# BV10011_ControlEtherCAT.net
KiCad netlist of a schematic drawn in Altium Designer
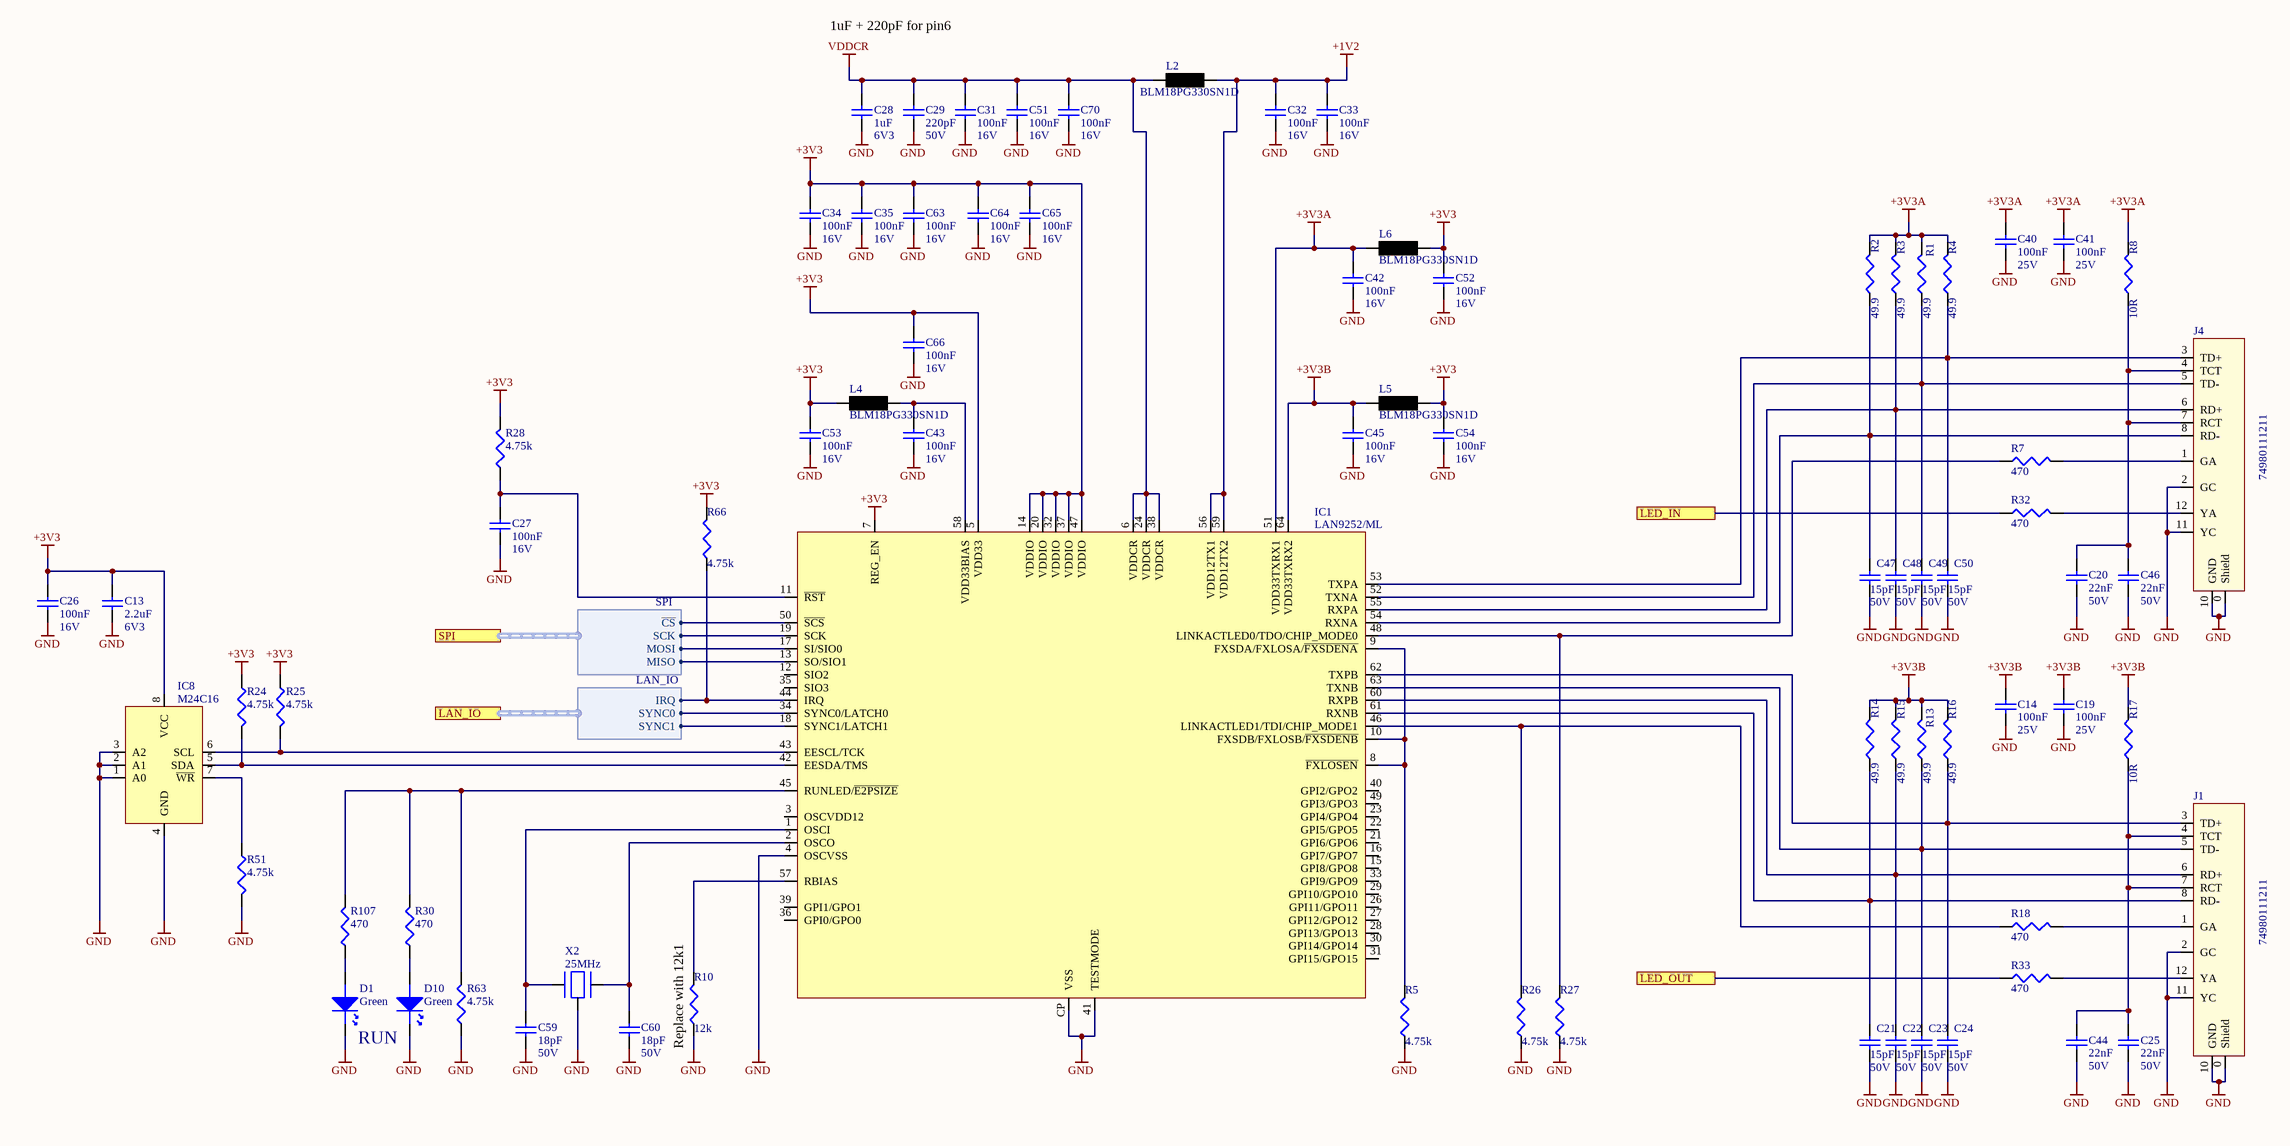
[diagram p0: BV10011_ControlEtherCAT.SchDoc]

(export (version "E")
  (design (tool "Eeschema 10.0.6"))
  (components
    (comp (ref "C13")
      (value "2.2uF")
      (footprint "C0402")
      (description "Capacitor, 2.2uF, 6.3V, X5R")
      (fields (field (name "VOLTAGE RATING") "6V3"))
      (libsource (lib "AR_Capacitors_Ceramic") (part "2.2uF/0402/CER/6.3V"))
    )
    (comp (ref "C14")
      (value "100nF")
      (footprint "C0402")
      (description "Capacitor, 100nF, 25V, X7R")
      (fields (field (name "VOLTAGE RATING") "25V"))
      (libsource (lib "AR_Capacitors_Ceramic") (part "100nF/0402/CER/25V"))
    )
    (comp (ref "C19")
      (value "100nF")
      (footprint "C0402")
      (description "Capacitor, 100nF, 25V, X7R")
      (fields (field (name "VOLTAGE RATING") "25V"))
      (libsource (lib "AR_Capacitors_Ceramic") (part "100nF/0402/CER/25V"))
    )
    (comp (ref "C20")
      (value "22nF")
      (footprint "C0402")
      (description "Capacitor, 22nF, 50V, X7R")
      (fields (field (name "VOLTAGE RATING") "50V"))
      (libsource (lib "AR_Capacitors_Ceramic") (part "22nF/0402/CER/50V"))
    )
    (comp (ref "C21")
      (value "15pF")
      (footprint "C0402")
      (description "Capacitor, 15pF, 50V, C0G")
      (fields (field (name "VOLTAGE RATING") "50V"))
      (libsource (lib "AR_Capacitors_Ceramic") (part "15pF/0402/CER/50V"))
    )
    (comp (ref "C22")
      (value "15pF")
      (footprint "C0402")
      (description "Capacitor, 15pF, 50V, C0G")
      (fields (field (name "VOLTAGE RATING") "50V"))
      (libsource (lib "AR_Capacitors_Ceramic") (part "15pF/0402/CER/50V"))
    )
    (comp (ref "C23")
      (value "15pF")
      (footprint "C0402")
      (description "Capacitor, 15pF, 50V, C0G")
      (fields (field (name "VOLTAGE RATING") "50V"))
      (libsource (lib "AR_Capacitors_Ceramic") (part "15pF/0402/CER/50V"))
    )
    (comp (ref "C24")
      (value "15pF")
      (footprint "C0402")
      (description "Capacitor, 15pF, 50V, C0G")
      (fields (field (name "VOLTAGE RATING") "50V"))
      (libsource (lib "AR_Capacitors_Ceramic") (part "15pF/0402/CER/50V"))
    )
    (comp (ref "C25")
      (value "22nF")
      (footprint "C0402")
      (description "Capacitor, 22nF, 50V, X7R")
      (fields (field (name "VOLTAGE RATING") "50V"))
      (libsource (lib "AR_Capacitors_Ceramic") (part "22nF/0402/CER/50V"))
    )
    (comp (ref "C26")
      (value "100nF")
      (footprint "C0402")
      (description "Capacitor, 100nF, 16V, X7R")
      (fields (field (name "VOLTAGE RATING") "16V"))
      (libsource (lib "AR_Capacitors_Ceramic") (part "100nF/0402/CER/16V"))
    )
    (comp (ref "C27")
      (value "100nF")
      (footprint "C0402")
      (description "Capacitor, 100nF, 16V, X7R")
      (fields (field (name "VOLTAGE RATING") "16V"))
      (libsource (lib "AR_Capacitors_Ceramic") (part "100nF/0402/CER/16V"))
    )
    (comp (ref "C28")
      (value "1uF")
      (footprint "C0402")
      (description "Capacitor, 1uF, 6.3V, X5R")
      (fields (field (name "VOLTAGE RATING") "6V3"))
      (libsource (lib "AR_Capacitors_Ceramic") (part "1uF/0402/CER/6.3V"))
    )
    (comp (ref "C29")
      (value "220pF")
      (footprint "C0402")
      (description "Capacitor, 220pF, 50V, NP0")
      (fields (field (name "VOLTAGE RATING") "50V"))
      (libsource (lib "AR_Capacitors_Ceramic") (part "220pF/0402/CER/50V"))
    )
    (comp (ref "C31")
      (value "100nF")
      (footprint "C0402")
      (description "Capacitor, 100nF, 16V, X7R")
      (fields (field (name "VOLTAGE RATING") "16V"))
      (libsource (lib "AR_Capacitors_Ceramic") (part "100nF/0402/CER/16V"))
    )
    (comp (ref "C32")
      (value "100nF")
      (footprint "C0402")
      (description "Capacitor, 100nF, 16V, X7R")
      (fields (field (name "VOLTAGE RATING") "16V"))
      (libsource (lib "AR_Capacitors_Ceramic") (part "100nF/0402/CER/16V"))
    )
    (comp (ref "C33")
      (value "100nF")
      (footprint "C0402")
      (description "Capacitor, 100nF, 16V, X7R")
      (fields (field (name "VOLTAGE RATING") "16V"))
      (libsource (lib "AR_Capacitors_Ceramic") (part "100nF/0402/CER/16V"))
    )
    (comp (ref "C34")
      (value "100nF")
      (footprint "C0402")
      (description "Capacitor, 100nF, 16V, X7R")
      (fields (field (name "VOLTAGE RATING") "16V"))
      (libsource (lib "AR_Capacitors_Ceramic") (part "100nF/0402/CER/16V"))
    )
    (comp (ref "C35")
      (value "100nF")
      (footprint "C0402")
      (description "Capacitor, 100nF, 16V, X7R")
      (fields (field (name "VOLTAGE RATING") "16V"))
      (libsource (lib "AR_Capacitors_Ceramic") (part "100nF/0402/CER/16V"))
    )
    (comp (ref "C40")
      (value "100nF")
      (footprint "C0402")
      (description "Capacitor, 100nF, 25V, X7R")
      (fields (field (name "VOLTAGE RATING") "25V"))
      (libsource (lib "AR_Capacitors_Ceramic") (part "100nF/0402/CER/25V"))
    )
    (comp (ref "C41")
      (value "100nF")
      (footprint "C0402")
      (description "Capacitor, 100nF, 25V, X7R")
      (fields (field (name "VOLTAGE RATING") "25V"))
      (libsource (lib "AR_Capacitors_Ceramic") (part "100nF/0402/CER/25V"))
    )
    (comp (ref "C42")
      (value "100nF")
      (footprint "C0402")
      (description "Capacitor, 100nF, 16V, X7R")
      (fields (field (name "VOLTAGE RATING") "16V"))
      (libsource (lib "AR_Capacitors_Ceramic") (part "100nF/0402/CER/16V"))
    )
    (comp (ref "C43")
      (value "100nF")
      (footprint "C0402")
      (description "Capacitor, 100nF, 16V, X7R")
      (fields (field (name "VOLTAGE RATING") "16V"))
      (libsource (lib "AR_Capacitors_Ceramic") (part "100nF/0402/CER/16V"))
    )
    (comp (ref "C44")
      (value "22nF")
      (footprint "C0402")
      (description "Capacitor, 22nF, 50V, X7R")
      (fields (field (name "VOLTAGE RATING") "50V"))
      (libsource (lib "AR_Capacitors_Ceramic") (part "22nF/0402/CER/50V"))
    )
    (comp (ref "C45")
      (value "100nF")
      (footprint "C0402")
      (description "Capacitor, 100nF, 16V, X7R")
      (fields (field (name "VOLTAGE RATING") "16V"))
      (libsource (lib "AR_Capacitors_Ceramic") (part "100nF/0402/CER/16V"))
    )
    (comp (ref "C46")
      (value "22nF")
      (footprint "C0402")
      (description "Capacitor, 22nF, 50V, X7R")
      (fields (field (name "VOLTAGE RATING") "50V"))
      (libsource (lib "AR_Capacitors_Ceramic") (part "22nF/0402/CER/50V"))
    )
    (comp (ref "C47")
      (value "15pF")
      (footprint "C0402")
      (description "Capacitor, 15pF, 50V, C0G")
      (fields (field (name "VOLTAGE RATING") "50V"))
      (libsource (lib "AR_Capacitors_Ceramic") (part "15pF/0402/CER/50V"))
    )
    (comp (ref "C48")
      (value "15pF")
      (footprint "C0402")
      (description "Capacitor, 15pF, 50V, C0G")
      (fields (field (name "VOLTAGE RATING") "50V"))
      (libsource (lib "AR_Capacitors_Ceramic") (part "15pF/0402/CER/50V"))
    )
    (comp (ref "C49")
      (value "15pF")
      (footprint "C0402")
      (description "Capacitor, 15pF, 50V, C0G")
      (fields (field (name "VOLTAGE RATING") "50V"))
      (libsource (lib "AR_Capacitors_Ceramic") (part "15pF/0402/CER/50V"))
    )
    (comp (ref "C50")
      (value "15pF")
      (footprint "C0402")
      (description "Capacitor, 15pF, 50V, C0G")
      (fields (field (name "VOLTAGE RATING") "50V"))
      (libsource (lib "AR_Capacitors_Ceramic") (part "15pF/0402/CER/50V"))
    )
    (comp (ref "C51")
      (value "100nF")
      (footprint "C0402")
      (description "Capacitor, 100nF, 16V, X7R")
      (fields (field (name "VOLTAGE RATING") "16V"))
      (libsource (lib "AR_Capacitors_Ceramic") (part "100nF/0402/CER/16V"))
    )
    (comp (ref "C52")
      (value "100nF")
      (footprint "C0402")
      (description "Capacitor, 100nF, 16V, X7R")
      (fields (field (name "VOLTAGE RATING") "16V"))
      (libsource (lib "AR_Capacitors_Ceramic") (part "100nF/0402/CER/16V"))
    )
    (comp (ref "C53")
      (value "100nF")
      (footprint "C0402")
      (description "Capacitor, 100nF, 16V, X7R")
      (fields (field (name "VOLTAGE RATING") "16V"))
      (libsource (lib "AR_Capacitors_Ceramic") (part "100nF/0402/CER/16V"))
    )
    (comp (ref "C54")
      (value "100nF")
      (footprint "C0402")
      (description "Capacitor, 100nF, 16V, X7R")
      (fields (field (name "VOLTAGE RATING") "16V"))
      (libsource (lib "AR_Capacitors_Ceramic") (part "100nF/0402/CER/16V"))
    )
    (comp (ref "C59")
      (value "18pF")
      (footprint "C0402")
      (description "Capacitor, 18pF, 50V, NP0")
      (fields (field (name "VOLTAGE RATING") "50V"))
      (libsource (lib "AR_Capacitors_Ceramic") (part "18pF/0402/CER/50V"))
    )
    (comp (ref "C60")
      (value "18pF")
      (footprint "C0402")
      (description "Capacitor, 18pF, 50V, NP0")
      (fields (field (name "VOLTAGE RATING") "50V"))
      (libsource (lib "AR_Capacitors_Ceramic") (part "18pF/0402/CER/50V"))
    )
    (comp (ref "C63")
      (value "100nF")
      (footprint "C0402")
      (description "Capacitor, 100nF, 16V, X7R")
      (fields (field (name "VOLTAGE RATING") "16V"))
      (libsource (lib "AR_Capacitors_Ceramic") (part "100nF/0402/CER/16V"))
    )
    (comp (ref "C64")
      (value "100nF")
      (footprint "C0402")
      (description "Capacitor, 100nF, 16V, X7R")
      (fields (field (name "VOLTAGE RATING") "16V"))
      (libsource (lib "AR_Capacitors_Ceramic") (part "100nF/0402/CER/16V"))
    )
    (comp (ref "C65")
      (value "100nF")
      (footprint "C0402")
      (description "Capacitor, 100nF, 16V, X7R")
      (fields (field (name "VOLTAGE RATING") "16V"))
      (libsource (lib "AR_Capacitors_Ceramic") (part "100nF/0402/CER/16V"))
    )
    (comp (ref "C66")
      (value "100nF")
      (footprint "C0402")
      (description "Capacitor, 100nF, 16V, X7R")
      (fields (field (name "VOLTAGE RATING") "16V"))
      (libsource (lib "AR_Capacitors_Ceramic") (part "100nF/0402/CER/16V"))
    )
    (comp (ref "C70")
      (value "100nF")
      (footprint "C0402")
      (description "Capacitor, 100nF, 16V, X7R")
      (fields (field (name "VOLTAGE RATING") "16V"))
      (libsource (lib "AR_Capacitors_Ceramic") (part "100nF/0402/CER/16V"))
    )
    (comp (ref "D1")
      (value "Green")
      (footprint "D-0805")
      (description "Led, Green, Li:12mcd, Vf:2.2V, If:0.02A")
      (libsource (lib "AR_Misc") (part "KP-2012SGC"))
    )
    (comp (ref "D10")
      (value "Green")
      (footprint "D-0805")
      (description "Led, Green, Li:12mcd, Vf:2.2V, If:0.02A")
      (libsource (lib "AR_Misc") (part "KP-2012SGC"))
    )
    (comp (ref "IC1")
      (value "LAN9252/ML")
      (footprint "QFN64_Rect")
      (description "EtherCAT Slave Controller")
      (libsource (lib "AR_ICs") (part "LAN9252/ML"))
    )
    (comp (ref "IC8")
      (value "M24C16")
      (footprint "SO-8")
      (description "SERIAL EEPROM, 16KBIT, 400KHZ")
      (libsource (lib "AR_ICs") (part "M24C16-WMN6P"))
    )
    (comp (ref "J1")
      (value "74980111211")
      (footprint "74980111211")
      (description "RJ45 With LAN TRANSFRMR")
      (libsource (lib "AR_Connectors") (part "74980111211"))
    )
    (comp (ref "J4")
      (value "74980111211")
      (footprint "74980111211")
      (description "RJ45 With LAN TRANSFRMR")
      (libsource (lib "AR_Connectors") (part "74980111211"))
    )
    (comp (ref "L2")
      (value "BLM18PG330SN1D")
      (footprint "L0603")
      (description "Ferrite Bead, Impedance:33ohm, DC Resistance Max:0.025ohm, DC Current Rating:3A")
      (libsource (lib "AR_Inductors") (part "BLM18PG330SN1D"))
    )
    (comp (ref "L4")
      (value "BLM18PG330SN1D")
      (footprint "L0603")
      (description "Ferrite Bead, Impedance:33ohm, DC Resistance Max:0.025ohm, DC Current Rating:3A")
      (libsource (lib "") (part "BLM18PG330SN1D_1"))
    )
    (comp (ref "L5")
      (value "BLM18PG330SN1D")
      (footprint "L0603")
      (description "Ferrite Bead, Impedance:33ohm, DC Resistance Max:0.025ohm, DC Current Rating:3A")
      (libsource (lib "AR_Inductors") (part "BLM18PG330SN1D"))
    )
    (comp (ref "L6")
      (value "BLM18PG330SN1D")
      (footprint "L0603")
      (description "Ferrite Bead, Impedance:33ohm, DC Resistance Max:0.025ohm, DC Current Rating:3A")
      (libsource (lib "AR_Inductors") (part "BLM18PG330SN1D"))
    )
    (comp (ref "R1")
      (value "49.9")
      (footprint "0402")
      (description "Resistor, 49.9, 0.1%, 0.0625W, 50V, 100PPM, 0402")
      (libsource (lib "AR_Resistors_SMD") (part "49.9/0402/0063W/50V"))
    )
    (comp (ref "R2")
      (value "49.9")
      (footprint "0402")
      (description "Resistor, 49.9, 0.1%, 0.0625W, 50V, 100PPM, 0402")
      (libsource (lib "AR_Resistors_SMD") (part "49.9/0402/0063W/50V"))
    )
    (comp (ref "R3")
      (value "49.9")
      (footprint "0402")
      (description "Resistor, 49.9, 0.1%, 0.0625W, 50V, 100PPM, 0402")
      (libsource (lib "AR_Resistors_SMD") (part "49.9/0402/0063W/50V"))
    )
    (comp (ref "R4")
      (value "49.9")
      (footprint "0402")
      (description "Resistor, 49.9, 0.1%, 0.0625W, 50V, 100PPM, 0402")
      (libsource (lib "AR_Resistors_SMD") (part "49.9/0402/0063W/50V"))
    )
    (comp (ref "R5")
      (value "4.75k")
      (footprint "0402")
      (description "Resistor, 4.75k, 0.1%, 0.0625W, 50V, 100PPM, 0402")
      (libsource (lib "AR_Resistors_SMD") (part "4.75k/0402/0063W/50V"))
    )
    (comp (ref "R7")
      (value "470")
      (footprint "0402")
      (description "Resistor, 470, 1%, 0.0625W, 50V, 100PPM, 0402")
      (libsource (lib "AR_Resistors_SMD") (part "470/0402/0063W/50V"))
    )
    (comp (ref "R8")
      (value "10R")
      (footprint "0603")
      (description "Resistor, 10R, 1%, 0.125W, 50V, 200PPM, 0603")
      (libsource (lib "AR_Resistors_SMD") (part "10/0603/0125W/50V"))
    )
    (comp (ref "R10")
      (value "12k")
      (footprint "0402")
      (description "Resistor, 12k, 1%, 0.0625W, 50V, 100PPM, 0402")
      (libsource (lib "AR_Resistors_SMD") (part "12k/0402/0063W/50V"))
    )
    (comp (ref "R13")
      (value "49.9")
      (footprint "0402")
      (description "Resistor, 49.9, 0.1%, 0.0625W, 50V, 100PPM, 0402")
      (libsource (lib "AR_Resistors_SMD") (part "49.9/0402/0063W/50V"))
    )
    (comp (ref "R14")
      (value "49.9")
      (footprint "0402")
      (description "Resistor, 49.9, 0.1%, 0.0625W, 50V, 100PPM, 0402")
      (libsource (lib "AR_Resistors_SMD") (part "49.9/0402/0063W/50V"))
    )
    (comp (ref "R15")
      (value "49.9")
      (footprint "0402")
      (description "Resistor, 49.9, 0.1%, 0.0625W, 50V, 100PPM, 0402")
      (libsource (lib "AR_Resistors_SMD") (part "49.9/0402/0063W/50V"))
    )
    (comp (ref "R16")
      (value "49.9")
      (footprint "0402")
      (description "Resistor, 49.9, 0.1%, 0.0625W, 50V, 100PPM, 0402")
      (libsource (lib "AR_Resistors_SMD") (part "49.9/0402/0063W/50V"))
    )
    (comp (ref "R17")
      (value "10R")
      (footprint "0603")
      (description "Resistor, 10R, 1%, 0.125W, 50V, 200PPM, 0603")
      (libsource (lib "AR_Resistors_SMD") (part "10/0603/0125W/50V"))
    )
    (comp (ref "R18")
      (value "470")
      (footprint "0402")
      (description "Resistor, 470, 1%, 0.0625W, 50V, 100PPM, 0402")
      (libsource (lib "AR_Resistors_SMD") (part "470/0402/0063W/50V"))
    )
    (comp (ref "R24")
      (value "4.75k")
      (footprint "0402")
      (description "Resistor, 4.75k, 0.1%, 0.0625W, 50V, 100PPM, 0402")
      (libsource (lib "AR_Resistors_SMD") (part "4.75k/0402/0063W/50V"))
    )
    (comp (ref "R25")
      (value "4.75k")
      (footprint "0402")
      (description "Resistor, 4.75k, 0.1%, 0.0625W, 50V, 100PPM, 0402")
      (libsource (lib "AR_Resistors_SMD") (part "4.75k/0402/0063W/50V"))
    )
    (comp (ref "R26")
      (value "4.75k")
      (footprint "0402")
      (description "Resistor, 4.75k, 0.1%, 0.0625W, 50V, 100PPM, 0402")
      (libsource (lib "AR_Resistors_SMD") (part "4.75k/0402/0063W/50V"))
    )
    (comp (ref "R27")
      (value "4.75k")
      (footprint "0402")
      (description "Resistor, 4.75k, 0.1%, 0.0625W, 50V, 100PPM, 0402")
      (libsource (lib "AR_Resistors_SMD") (part "4.75k/0402/0063W/50V"))
    )
    (comp (ref "R28")
      (value "4.75k")
      (footprint "0402")
      (description "Resistor, 4.75k, 0.1%, 0.0625W, 50V, 100PPM, 0402")
      (libsource (lib "AR_Resistors_SMD") (part "4.75k/0402/0063W/50V"))
    )
    (comp (ref "R30")
      (value "470")
      (footprint "0402")
      (description "Resistor, 470, 1%, 0.0625W, 50V, 100PPM, 0402")
      (libsource (lib "AR_Resistors_SMD") (part "470/0402/0063W/50V"))
    )
    (comp (ref "R32")
      (value "470")
      (footprint "0402")
      (description "Resistor, 470, 1%, 0.0625W, 50V, 100PPM, 0402")
      (libsource (lib "AR_Resistors_SMD") (part "470/0402/0063W/50V"))
    )
    (comp (ref "R33")
      (value "470")
      (footprint "0402")
      (description "Resistor, 470, 1%, 0.0625W, 50V, 100PPM, 0402")
      (libsource (lib "AR_Resistors_SMD") (part "470/0402/0063W/50V"))
    )
    (comp (ref "R51")
      (value "4.75k")
      (footprint "0402")
      (description "Resistor, 4.75k, 0.1%, 0.0625W, 50V, 100PPM, 0402")
      (libsource (lib "AR_Resistors_SMD") (part "4.75k/0402/0063W/50V"))
    )
    (comp (ref "R63")
      (value "4.75k")
      (footprint "0402")
      (description "Resistor, 4.75k, 0.1%, 0.0625W, 50V, 100PPM, 0402")
      (libsource (lib "AR_Resistors_SMD") (part "4.75k/0402/0063W/50V"))
    )
    (comp (ref "R66")
      (value "4.75k")
      (footprint "0402")
      (description "Resistor, 4.75k, 0.1%, 0.0625W, 50V, 100PPM, 0402")
      (libsource (lib "AR_Resistors_SMD") (part "4.75k/0402/0063W/50V"))
    )
    (comp (ref "R107")
      (value "470")
      (footprint "0402")
      (description "Resistor, 470, 1%, 0.0625W, 50V, 100PPM, 0402")
      (libsource (lib "AR_Resistors_SMD") (part "470/0402/0063W/50V"))
    )
    (comp (ref "X2")
      (value "25MHz")
      (footprint "7M")
      (description "CRYSTAL, 25MHz,18PF CL, 3.2X2.5MM SMT")
      (libsource (lib "AR_Crystals") (part "7M-25.000MAAJ-T"))
    )
  )
  (nets
    (net (code "3") (name "+1V2") (class "Default")
      (node (ref "C32") (pin "2") (pinfunction "2_2") (pintype "passive"))
      (node (ref "C33") (pin "2") (pinfunction "2_2") (pintype "passive"))
      (node (ref "IC1") (pin "56") (pinfunction "VDD12TX1_56") (pintype "passive"))
      (node (ref "IC1") (pin "59") (pinfunction "VDD12TX2_59") (pintype "passive"))
      (node (ref "L2") (pin "2") (pinfunction "2_2") (pintype "passive"))
    )
    (net (code "4") (name "+3V3") (class "Default")
      (node (ref "C13") (pin "2") (pinfunction "2_2") (pintype "passive"))
      (node (ref "C26") (pin "2") (pinfunction "2_2") (pintype "passive"))
      (node (ref "C34") (pin "2") (pinfunction "2_2") (pintype "passive"))
      (node (ref "C35") (pin "2") (pinfunction "2_2") (pintype "passive"))
      (node (ref "C52") (pin "2") (pinfunction "2_2") (pintype "passive"))
      (node (ref "C53") (pin "2") (pinfunction "2_2") (pintype "passive"))
      (node (ref "C54") (pin "2") (pinfunction "2_2") (pintype "passive"))
      (node (ref "C63") (pin "2") (pinfunction "2_2") (pintype "passive"))
      (node (ref "C64") (pin "2") (pinfunction "2_2") (pintype "passive"))
      (node (ref "C65") (pin "2") (pinfunction "2_2") (pintype "passive"))
      (node (ref "C66") (pin "2") (pinfunction "2_2") (pintype "passive"))
      (node (ref "IC1") (pin "14") (pinfunction "VDDIO_14") (pintype "passive"))
      (node (ref "IC1") (pin "20") (pinfunction "VDDIO_20") (pintype "passive"))
      (node (ref "IC1") (pin "32") (pinfunction "VDDIO_32") (pintype "passive"))
      (node (ref "IC1") (pin "37") (pinfunction "VDDIO_37") (pintype "passive"))
      (node (ref "IC1") (pin "47") (pinfunction "VDDIO_47") (pintype "passive"))
      (node (ref "IC1") (pin "5") (pinfunction "VDD33_5") (pintype "passive"))
      (node (ref "IC1") (pin "7") (pinfunction "REG_EN_7") (pintype "passive"))
      (node (ref "IC8") (pin "8") (pinfunction "VCC_8") (pintype "passive"))
      (node (ref "L4") (pin "2") (pinfunction "2_2") (pintype "passive"))
      (node (ref "L5") (pin "2") (pinfunction "2_2") (pintype "passive"))
      (node (ref "L6") (pin "2") (pinfunction "2_2") (pintype "passive"))
      (node (ref "R24") (pin "2") (pinfunction "2_2") (pintype "passive"))
      (node (ref "R25") (pin "2") (pinfunction "2_2") (pintype "passive"))
      (node (ref "R28") (pin "2") (pinfunction "2_2") (pintype "passive"))
      (node (ref "R66") (pin "2") (pinfunction "2_2") (pintype "passive"))
    )
    (net (code "5") (name "+3V3A") (class "Default")
      (node (ref "C40") (pin "2") (pinfunction "2_2") (pintype "passive"))
      (node (ref "C41") (pin "2") (pinfunction "2_2") (pintype "passive"))
      (node (ref "C42") (pin "2") (pinfunction "2_2") (pintype "passive"))
      (node (ref "IC1") (pin "51") (pinfunction "VDD33TXRX1_51") (pintype "passive"))
      (node (ref "L6") (pin "1") (pinfunction "1_1") (pintype "passive"))
      (node (ref "R1") (pin "2") (pinfunction "2_2") (pintype "passive"))
      (node (ref "R2") (pin "2") (pinfunction "2_2") (pintype "passive"))
      (node (ref "R3") (pin "2") (pinfunction "2_2") (pintype "passive"))
      (node (ref "R4") (pin "2") (pinfunction "2_2") (pintype "passive"))
      (node (ref "R8") (pin "2") (pinfunction "2_2") (pintype "passive"))
    )
    (net (code "6") (name "+3V3B") (class "Default")
      (node (ref "C14") (pin "2") (pinfunction "2_2") (pintype "passive"))
      (node (ref "C19") (pin "2") (pinfunction "2_2") (pintype "passive"))
      (node (ref "C45") (pin "2") (pinfunction "2_2") (pintype "passive"))
      (node (ref "IC1") (pin "64") (pinfunction "VDD33TXRX2_64") (pintype "passive"))
      (node (ref "L5") (pin "1") (pinfunction "1_1") (pintype "passive"))
      (node (ref "R13") (pin "2") (pinfunction "2_2") (pintype "passive"))
      (node (ref "R14") (pin "2") (pinfunction "2_2") (pintype "passive"))
      (node (ref "R15") (pin "2") (pinfunction "2_2") (pintype "passive"))
      (node (ref "R16") (pin "2") (pinfunction "2_2") (pintype "passive"))
      (node (ref "R17") (pin "2") (pinfunction "2_2") (pintype "passive"))
    )
    (net (code "7") (name "/IRQ") (class "Default")
      (node (ref "IC1") (pin "44") (pinfunction "IRQ_44") (pintype "passive"))
      (node (ref "R66") (pin "1") (pinfunction "1_1") (pintype "passive"))
    )
    (net (code "8") (name "/LED_IN") (class "Default")
      (node (ref "R32") (pin "1") (pinfunction "1_1") (pintype "passive"))
    )
    (net (code "9") (name "/LED_OUT") (class "Default")
      (node (ref "R33") (pin "1") (pinfunction "1_1") (pintype "passive"))
    )
    (net (code "10") (name "/MISO") (class "Default")
      (node (ref "IC1") (pin "13") (pinfunction "SO/SIO1_13") (pintype "passive"))
    )
    (net (code "11") (name "/MOSI") (class "Default")
      (node (ref "IC1") (pin "17") (pinfunction "SI/SIO0_17") (pintype "passive"))
    )
    (net (code "12") (name "/SCK") (class "Default")
      (node (ref "IC1") (pin "19") (pinfunction "SCK_19") (pintype "passive"))
    )
    (net (code "13") (name "/SYNC0") (class "Default")
      (node (ref "IC1") (pin "34") (pinfunction "SYNC0/LATCH0_34") (pintype "passive"))
    )
    (net (code "14") (name "/SYNC1") (class "Default")
      (node (ref "IC1") (pin "18") (pinfunction "SYNC1/LATCH1_18") (pintype "passive"))
    )
    (net (code "17") (name "/~{CS}") (class "Default")
      (node (ref "IC1") (pin "50") (pinfunction "~{SCS}_50") (pintype "passive"))
    )
    (net (code "18") (name "GND") (class "Default")
      (node (ref "C13") (pin "1") (pinfunction "1_1") (pintype "passive"))
      (node (ref "C14") (pin "1") (pinfunction "1_1") (pintype "passive"))
      (node (ref "C19") (pin "1") (pinfunction "1_1") (pintype "passive"))
      (node (ref "C20") (pin "1") (pinfunction "1_1") (pintype "passive"))
      (node (ref "C21") (pin "1") (pinfunction "1_1") (pintype "passive"))
      (node (ref "C22") (pin "1") (pinfunction "1_1") (pintype "passive"))
      (node (ref "C23") (pin "1") (pinfunction "1_1") (pintype "passive"))
      (node (ref "C24") (pin "1") (pinfunction "1_1") (pintype "passive"))
      (node (ref "C25") (pin "1") (pinfunction "1_1") (pintype "passive"))
      (node (ref "C26") (pin "1") (pinfunction "1_1") (pintype "passive"))
      (node (ref "C27") (pin "1") (pinfunction "1_1") (pintype "passive"))
      (node (ref "C28") (pin "1") (pinfunction "1_1") (pintype "passive"))
      (node (ref "C29") (pin "1") (pinfunction "1_1") (pintype "passive"))
      (node (ref "C31") (pin "1") (pinfunction "1_1") (pintype "passive"))
      (node (ref "C32") (pin "1") (pinfunction "1_1") (pintype "passive"))
      (node (ref "C33") (pin "1") (pinfunction "1_1") (pintype "passive"))
      (node (ref "C34") (pin "1") (pinfunction "1_1") (pintype "passive"))
      (node (ref "C35") (pin "1") (pinfunction "1_1") (pintype "passive"))
      (node (ref "C40") (pin "1") (pinfunction "1_1") (pintype "passive"))
      (node (ref "C41") (pin "1") (pinfunction "1_1") (pintype "passive"))
      (node (ref "C42") (pin "1") (pinfunction "1_1") (pintype "passive"))
      (node (ref "C43") (pin "1") (pinfunction "1_1") (pintype "passive"))
      (node (ref "C44") (pin "1") (pinfunction "1_1") (pintype "passive"))
      (node (ref "C45") (pin "1") (pinfunction "1_1") (pintype "passive"))
      (node (ref "C46") (pin "1") (pinfunction "1_1") (pintype "passive"))
      (node (ref "C47") (pin "1") (pinfunction "1_1") (pintype "passive"))
      (node (ref "C48") (pin "1") (pinfunction "1_1") (pintype "passive"))
      (node (ref "C49") (pin "1") (pinfunction "1_1") (pintype "passive"))
      (node (ref "C50") (pin "1") (pinfunction "1_1") (pintype "passive"))
      (node (ref "C51") (pin "1") (pinfunction "1_1") (pintype "passive"))
      (node (ref "C52") (pin "1") (pinfunction "1_1") (pintype "passive"))
      (node (ref "C53") (pin "1") (pinfunction "1_1") (pintype "passive"))
      (node (ref "C54") (pin "1") (pinfunction "1_1") (pintype "passive"))
      (node (ref "C59") (pin "1") (pinfunction "1_1") (pintype "passive"))
      (node (ref "C60") (pin "1") (pinfunction "1_1") (pintype "passive"))
      (node (ref "C63") (pin "1") (pinfunction "1_1") (pintype "passive"))
      (node (ref "C64") (pin "1") (pinfunction "1_1") (pintype "passive"))
      (node (ref "C65") (pin "1") (pinfunction "1_1") (pintype "passive"))
      (node (ref "C66") (pin "1") (pinfunction "1_1") (pintype "passive"))
      (node (ref "C70") (pin "1") (pinfunction "1_1") (pintype "passive"))
      (node (ref "D1") (pin "K") (pinfunction "K_K") (pintype "passive"))
      (node (ref "D10") (pin "K") (pinfunction "K_K") (pintype "passive"))
      (node (ref "IC1") (pin "4") (pinfunction "OSCVSS_4") (pintype "passive"))
      (node (ref "IC1") (pin "41") (pinfunction "TESTMODE_41") (pintype "passive"))
      (node (ref "IC1") (pin "CP") (pinfunction "VSS_CP") (pintype "passive"))
      (node (ref "IC8") (pin "1") (pinfunction "A0_1") (pintype "passive"))
      (node (ref "IC8") (pin "2") (pinfunction "A1_2") (pintype "passive"))
      (node (ref "IC8") (pin "3") (pinfunction "A2_3") (pintype "passive"))
      (node (ref "IC8") (pin "4") (pinfunction "GND_4") (pintype "passive"))
      (node (ref "J1") (pin "0") (pinfunction "Shield_0") (pintype "passive"))
      (node (ref "J1") (pin "10") (pinfunction "GND_10") (pintype "passive"))
      (node (ref "J1") (pin "11") (pinfunction "YC_11") (pintype "passive"))
      (node (ref "J1") (pin "2") (pinfunction "GC_2") (pintype "passive"))
      (node (ref "J4") (pin "0") (pinfunction "Shield_0") (pintype "passive"))
      (node (ref "J4") (pin "10") (pinfunction "GND_10") (pintype "passive"))
      (node (ref "J4") (pin "11") (pinfunction "YC_11") (pintype "passive"))
      (node (ref "J4") (pin "2") (pinfunction "GC_2") (pintype "passive"))
      (node (ref "R10") (pin "1") (pinfunction "1_1") (pintype "passive"))
      (node (ref "R26") (pin "1") (pinfunction "1_1") (pintype "passive"))
      (node (ref "R27") (pin "1") (pinfunction "1_1") (pintype "passive"))
      (node (ref "R5") (pin "1") (pinfunction "1_1") (pintype "passive"))
      (node (ref "R51") (pin "1") (pinfunction "1_1") (pintype "passive"))
      (node (ref "R63") (pin "1") (pinfunction "1_1") (pintype "passive"))
      (node (ref "X2") (pin "0") (pinfunction "0_0") (pintype "power_in"))
    )
    (net (code "19") (name "Net-(D1-PadA)") (class "Default")
      (node (ref "D1") (pin "A") (pinfunction "A_A") (pintype "passive"))
      (node (ref "R107") (pin "1") (pinfunction "1_1") (pintype "passive"))
    )
    (net (code "20") (name "Net-(D10-PadA)") (class "Default")
      (node (ref "D10") (pin "A") (pinfunction "A_A") (pintype "passive"))
      (node (ref "R30") (pin "1") (pinfunction "1_1") (pintype "passive"))
    )
    (net (code "21") (name "Net-(IC1-EESCL{slash}TCK)") (class "Default")
      (node (ref "IC1") (pin "43") (pinfunction "EESCL/TCK_43") (pintype "passive"))
      (node (ref "IC8") (pin "6") (pinfunction "SCL_6") (pintype "passive"))
      (node (ref "R25") (pin "1") (pinfunction "1_1") (pintype "passive"))
    )
    (net (code "22") (name "Net-(IC1-EESDA{slash}TMS)") (class "Default")
      (node (ref "IC1") (pin "42") (pinfunction "EESDA/TMS_42") (pintype "passive"))
      (node (ref "IC8") (pin "5") (pinfunction "SDA_5") (pintype "passive"))
      (node (ref "R24") (pin "1") (pinfunction "1_1") (pintype "passive"))
    )
    (net (code "23") (name "Net-(IC1-FXSDA{slash}FXLOSA{slash}~{FXSDENA})") (class "Default")
      (node (ref "IC1") (pin "10") (pinfunction "FXSDB/FXLOSB/~{FXSDENB}_10") (pintype "passive"))
      (node (ref "IC1") (pin "8") (pinfunction "~{FXLOSEN}_8") (pintype "passive"))
      (node (ref "IC1") (pin "9") (pinfunction "FXSDA/FXLOSA/~{FXSDENA}_9") (pintype "passive"))
      (node (ref "R5") (pin "2") (pinfunction "2_2") (pintype "passive"))
    )
    (net (code "24") (name "Net-(IC1-LINKACTLED0{slash}TDO{slash}CHIP_MODE0)") (class "Default")
      (node (ref "IC1") (pin "48") (pinfunction "LINKACTLED0/TDO/CHIP_MODE0_48") (pintype "passive"))
      (node (ref "R27") (pin "2") (pinfunction "2_2") (pintype "passive"))
      (node (ref "R7") (pin "1") (pinfunction "1_1") (pintype "passive"))
    )
    (net (code "25") (name "Net-(IC1-LINKACTLED1{slash}TDI{slash}CHIP_MODE1)") (class "Default")
      (node (ref "IC1") (pin "46") (pinfunction "LINKACTLED1/TDI/CHIP_MODE1_46") (pintype "passive"))
      (node (ref "R18") (pin "1") (pinfunction "1_1") (pintype "passive"))
      (node (ref "R26") (pin "2") (pinfunction "2_2") (pintype "passive"))
    )
    (net (code "26") (name "Net-(IC1-OSCI)") (class "Default")
      (node (ref "C59") (pin "2") (pinfunction "2_2") (pintype "passive"))
      (node (ref "IC1") (pin "1") (pinfunction "OSCI_1") (pintype "passive"))
      (node (ref "X2") (pin "1") (pinfunction "1_1") (pintype "passive"))
    )
    (net (code "27") (name "Net-(IC1-OSCO)") (class "Default")
      (node (ref "C60") (pin "2") (pinfunction "2_2") (pintype "passive"))
      (node (ref "IC1") (pin "2") (pinfunction "OSCO_2") (pintype "passive"))
      (node (ref "X2") (pin "2") (pinfunction "2_2") (pintype "passive"))
    )
    (net (code "28") (name "Net-(IC1-RBIAS)") (class "Default")
      (node (ref "IC1") (pin "57") (pinfunction "RBIAS_57") (pintype "passive"))
      (node (ref "R10") (pin "2") (pinfunction "2_2") (pintype "passive"))
    )
    (net (code "29") (name "Net-(IC1-RUNLED{slash}~{E2PSIZE})") (class "Default")
      (node (ref "IC1") (pin "45") (pinfunction "RUNLED/~{E2PSIZE}_45") (pintype "passive"))
      (node (ref "R107") (pin "2") (pinfunction "2_2") (pintype "passive"))
      (node (ref "R30") (pin "2") (pinfunction "2_2") (pintype "passive"))
      (node (ref "R63") (pin "2") (pinfunction "2_2") (pintype "passive"))
    )
    (net (code "30") (name "Net-(IC1-RXNA)") (class "Default")
      (node (ref "C47") (pin "2") (pinfunction "2_2") (pintype "passive"))
      (node (ref "IC1") (pin "54") (pinfunction "RXNA_54") (pintype "passive"))
      (node (ref "J4") (pin "8") (pinfunction "RD-_8") (pintype "passive"))
      (node (ref "R2") (pin "1") (pinfunction "1_1") (pintype "passive"))
    )
    (net (code "31") (name "Net-(IC1-RXNB)") (class "Default")
      (node (ref "C21") (pin "2") (pinfunction "2_2") (pintype "passive"))
      (node (ref "IC1") (pin "61") (pinfunction "RXNB_61") (pintype "passive"))
      (node (ref "J1") (pin "8") (pinfunction "RD-_8") (pintype "passive"))
      (node (ref "R14") (pin "1") (pinfunction "1_1") (pintype "passive"))
    )
    (net (code "32") (name "Net-(IC1-RXPA)") (class "Default")
      (node (ref "C48") (pin "2") (pinfunction "2_2") (pintype "passive"))
      (node (ref "IC1") (pin "55") (pinfunction "RXPA_55") (pintype "passive"))
      (node (ref "J4") (pin "6") (pinfunction "RD+_6") (pintype "passive"))
      (node (ref "R3") (pin "1") (pinfunction "1_1") (pintype "passive"))
    )
    (net (code "33") (name "Net-(IC1-RXPB)") (class "Default")
      (node (ref "C22") (pin "2") (pinfunction "2_2") (pintype "passive"))
      (node (ref "IC1") (pin "60") (pinfunction "RXPB_60") (pintype "passive"))
      (node (ref "J1") (pin "6") (pinfunction "RD+_6") (pintype "passive"))
      (node (ref "R15") (pin "1") (pinfunction "1_1") (pintype "passive"))
    )
    (net (code "34") (name "Net-(IC1-TXNA)") (class "Default")
      (node (ref "C49") (pin "2") (pinfunction "2_2") (pintype "passive"))
      (node (ref "IC1") (pin "52") (pinfunction "TXNA_52") (pintype "passive"))
      (node (ref "J4") (pin "5") (pinfunction "TD-_5") (pintype "passive"))
      (node (ref "R1") (pin "1") (pinfunction "1_1") (pintype "passive"))
    )
    (net (code "35") (name "Net-(IC1-TXNB)") (class "Default")
      (node (ref "C23") (pin "2") (pinfunction "2_2") (pintype "passive"))
      (node (ref "IC1") (pin "63") (pinfunction "TXNB_63") (pintype "passive"))
      (node (ref "J1") (pin "5") (pinfunction "TD-_5") (pintype "passive"))
      (node (ref "R13") (pin "1") (pinfunction "1_1") (pintype "passive"))
    )
    (net (code "36") (name "Net-(IC1-TXPA)") (class "Default")
      (node (ref "C50") (pin "2") (pinfunction "2_2") (pintype "passive"))
      (node (ref "IC1") (pin "53") (pinfunction "TXPA_53") (pintype "passive"))
      (node (ref "J4") (pin "3") (pinfunction "TD+_3") (pintype "passive"))
      (node (ref "R4") (pin "1") (pinfunction "1_1") (pintype "passive"))
    )
    (net (code "37") (name "Net-(IC1-TXPB)") (class "Default")
      (node (ref "C24") (pin "2") (pinfunction "2_2") (pintype "passive"))
      (node (ref "IC1") (pin "62") (pinfunction "TXPB_62") (pintype "passive"))
      (node (ref "J1") (pin "3") (pinfunction "TD+_3") (pintype "passive"))
      (node (ref "R16") (pin "1") (pinfunction "1_1") (pintype "passive"))
    )
    (net (code "38") (name "Net-(IC1-VDD33BIAS)") (class "Default")
      (node (ref "C43") (pin "2") (pinfunction "2_2") (pintype "passive"))
      (node (ref "IC1") (pin "58") (pinfunction "VDD33BIAS_58") (pintype "passive"))
      (node (ref "L4") (pin "1") (pinfunction "1_1") (pintype "passive"))
    )
    (net (code "39") (name "Net-(IC1-~{RST})") (class "Default")
      (node (ref "C27") (pin "2") (pinfunction "2_2") (pintype "passive"))
      (node (ref "IC1") (pin "11") (pinfunction "~{RST}_11") (pintype "passive"))
      (node (ref "R28") (pin "1") (pinfunction "1_1") (pintype "passive"))
    )
    (net (code "40") (name "Net-(IC8-~{WR})") (class "Default")
      (node (ref "IC8") (pin "7") (pinfunction "~{WR}_7") (pintype "passive"))
      (node (ref "R51") (pin "2") (pinfunction "2_2") (pintype "passive"))
    )
    (net (code "41") (name "Net-(J1-GA)") (class "Default")
      (node (ref "J1") (pin "1") (pinfunction "GA_1") (pintype "passive"))
      (node (ref "R18") (pin "2") (pinfunction "2_2") (pintype "passive"))
    )
    (net (code "42") (name "Net-(J1-RCT)") (class "Default")
      (node (ref "C25") (pin "2") (pinfunction "2_2") (pintype "passive"))
      (node (ref "C44") (pin "2") (pinfunction "2_2") (pintype "passive"))
      (node (ref "J1") (pin "4") (pinfunction "TCT_4") (pintype "passive"))
      (node (ref "J1") (pin "7") (pinfunction "RCT_7") (pintype "passive"))
      (node (ref "R17") (pin "1") (pinfunction "1_1") (pintype "passive"))
    )
    (net (code "43") (name "Net-(J1-YA)") (class "Default")
      (node (ref "J1") (pin "12") (pinfunction "YA_12") (pintype "passive"))
      (node (ref "R33") (pin "2") (pinfunction "2_2") (pintype "passive"))
    )
    (net (code "44") (name "Net-(J4-GA)") (class "Default")
      (node (ref "J4") (pin "1") (pinfunction "GA_1") (pintype "passive"))
      (node (ref "R7") (pin "2") (pinfunction "2_2") (pintype "passive"))
    )
    (net (code "45") (name "Net-(J4-RCT)") (class "Default")
      (node (ref "C20") (pin "2") (pinfunction "2_2") (pintype "passive"))
      (node (ref "C46") (pin "2") (pinfunction "2_2") (pintype "passive"))
      (node (ref "J4") (pin "4") (pinfunction "TCT_4") (pintype "passive"))
      (node (ref "J4") (pin "7") (pinfunction "RCT_7") (pintype "passive"))
      (node (ref "R8") (pin "1") (pinfunction "1_1") (pintype "passive"))
    )
    (net (code "46") (name "Net-(J4-YA)") (class "Default")
      (node (ref "J4") (pin "12") (pinfunction "YA_12") (pintype "passive"))
      (node (ref "R32") (pin "2") (pinfunction "2_2") (pintype "passive"))
    )
    (net (code "47") (name "VDDCR") (class "Default")
      (node (ref "C28") (pin "2") (pinfunction "2_2") (pintype "passive"))
      (node (ref "C29") (pin "2") (pinfunction "2_2") (pintype "passive"))
      (node (ref "C31") (pin "2") (pinfunction "2_2") (pintype "passive"))
      (node (ref "C51") (pin "2") (pinfunction "2_2") (pintype "passive"))
      (node (ref "C70") (pin "2") (pinfunction "2_2") (pintype "passive"))
      (node (ref "IC1") (pin "24") (pinfunction "VDDCR_24") (pintype "passive"))
      (node (ref "IC1") (pin "38") (pinfunction "VDDCR_38") (pintype "passive"))
      (node (ref "IC1") (pin "6") (pinfunction "VDDCR_6") (pintype "passive"))
      (node (ref "L2") (pin "1") (pinfunction "1_1") (pintype "passive"))
    )
    (net (code "48") (name "unconnected-(IC1-GPI0{slash}GPO0-Pad36)") (class "Default")
      (node (ref "IC1") (pin "36") (pinfunction "GPI0/GPO0_36") (pintype "passive"))
    )
    (net (code "49") (name "unconnected-(IC1-GPI1{slash}GPO1-Pad39)") (class "Default")
      (node (ref "IC1") (pin "39") (pinfunction "GPI1/GPO1_39") (pintype "passive"))
    )
    (net (code "50") (name "unconnected-(IC1-GPI2{slash}GPO2-Pad40)") (class "Default")
      (node (ref "IC1") (pin "40") (pinfunction "GPI2/GPO2_40") (pintype "passive"))
    )
    (net (code "51") (name "unconnected-(IC1-GPI3{slash}GPO3-Pad49)") (class "Default")
      (node (ref "IC1") (pin "49") (pinfunction "GPI3/GPO3_49") (pintype "passive"))
    )
    (net (code "52") (name "unconnected-(IC1-GPI4{slash}GPO4-Pad23)") (class "Default")
      (node (ref "IC1") (pin "23") (pinfunction "GPI4/GPO4_23") (pintype "passive"))
    )
    (net (code "53") (name "unconnected-(IC1-GPI5{slash}GPO5-Pad22)") (class "Default")
      (node (ref "IC1") (pin "22") (pinfunction "GPI5/GPO5_22") (pintype "passive"))
    )
    (net (code "54") (name "unconnected-(IC1-GPI6{slash}GPO6-Pad21)") (class "Default")
      (node (ref "IC1") (pin "21") (pinfunction "GPI6/GPO6_21") (pintype "passive"))
    )
    (net (code "55") (name "unconnected-(IC1-GPI7{slash}GPO7-Pad16)") (class "Default")
      (node (ref "IC1") (pin "16") (pinfunction "GPI7/GPO7_16") (pintype "passive"))
    )
    (net (code "56") (name "unconnected-(IC1-GPI8{slash}GPO8-Pad15)") (class "Default")
      (node (ref "IC1") (pin "15") (pinfunction "GPI8/GPO8_15") (pintype "passive"))
    )
    (net (code "57") (name "unconnected-(IC1-GPI9{slash}GPO9-Pad33)") (class "Default")
      (node (ref "IC1") (pin "33") (pinfunction "GPI9/GPO9_33") (pintype "passive"))
    )
    (net (code "58") (name "unconnected-(IC1-GPI10{slash}GPO10-Pad29)") (class "Default")
      (node (ref "IC1") (pin "29") (pinfunction "GPI10/GPO10_29") (pintype "passive"))
    )
    (net (code "59") (name "unconnected-(IC1-GPI11{slash}GPO11-Pad26)") (class "Default")
      (node (ref "IC1") (pin "26") (pinfunction "GPI11/GPO11_26") (pintype "passive"))
    )
    (net (code "60") (name "unconnected-(IC1-GPI12{slash}GPO12-Pad27)") (class "Default")
      (node (ref "IC1") (pin "27") (pinfunction "GPI12/GPO12_27") (pintype "passive"))
    )
    (net (code "61") (name "unconnected-(IC1-GPI13{slash}GPO13-Pad28)") (class "Default")
      (node (ref "IC1") (pin "28") (pinfunction "GPI13/GPO13_28") (pintype "passive"))
    )
    (net (code "62") (name "unconnected-(IC1-GPI14{slash}GPO14-Pad30)") (class "Default")
      (node (ref "IC1") (pin "30") (pinfunction "GPI14/GPO14_30") (pintype "passive"))
    )
    (net (code "63") (name "unconnected-(IC1-GPI15{slash}GPO15-Pad31)") (class "Default")
      (node (ref "IC1") (pin "31") (pinfunction "GPI15/GPO15_31") (pintype "passive"))
    )
    (net (code "64") (name "unconnected-(IC1-OSCVDD12-Pad3)") (class "Default")
      (node (ref "IC1") (pin "3") (pinfunction "OSCVDD12_3") (pintype "passive"))
    )
    (net (code "65") (name "unconnected-(IC1-SIO2-Pad12)") (class "Default")
      (node (ref "IC1") (pin "12") (pinfunction "SIO2_12") (pintype "passive"))
    )
    (net (code "66") (name "unconnected-(IC1-SIO3-Pad35)") (class "Default")
      (node (ref "IC1") (pin "35") (pinfunction "SIO3_35") (pintype "passive"))
    )
  )
)
